# hw_interface_board.net
KiCad netlist of a schematic drawn in EAGLE
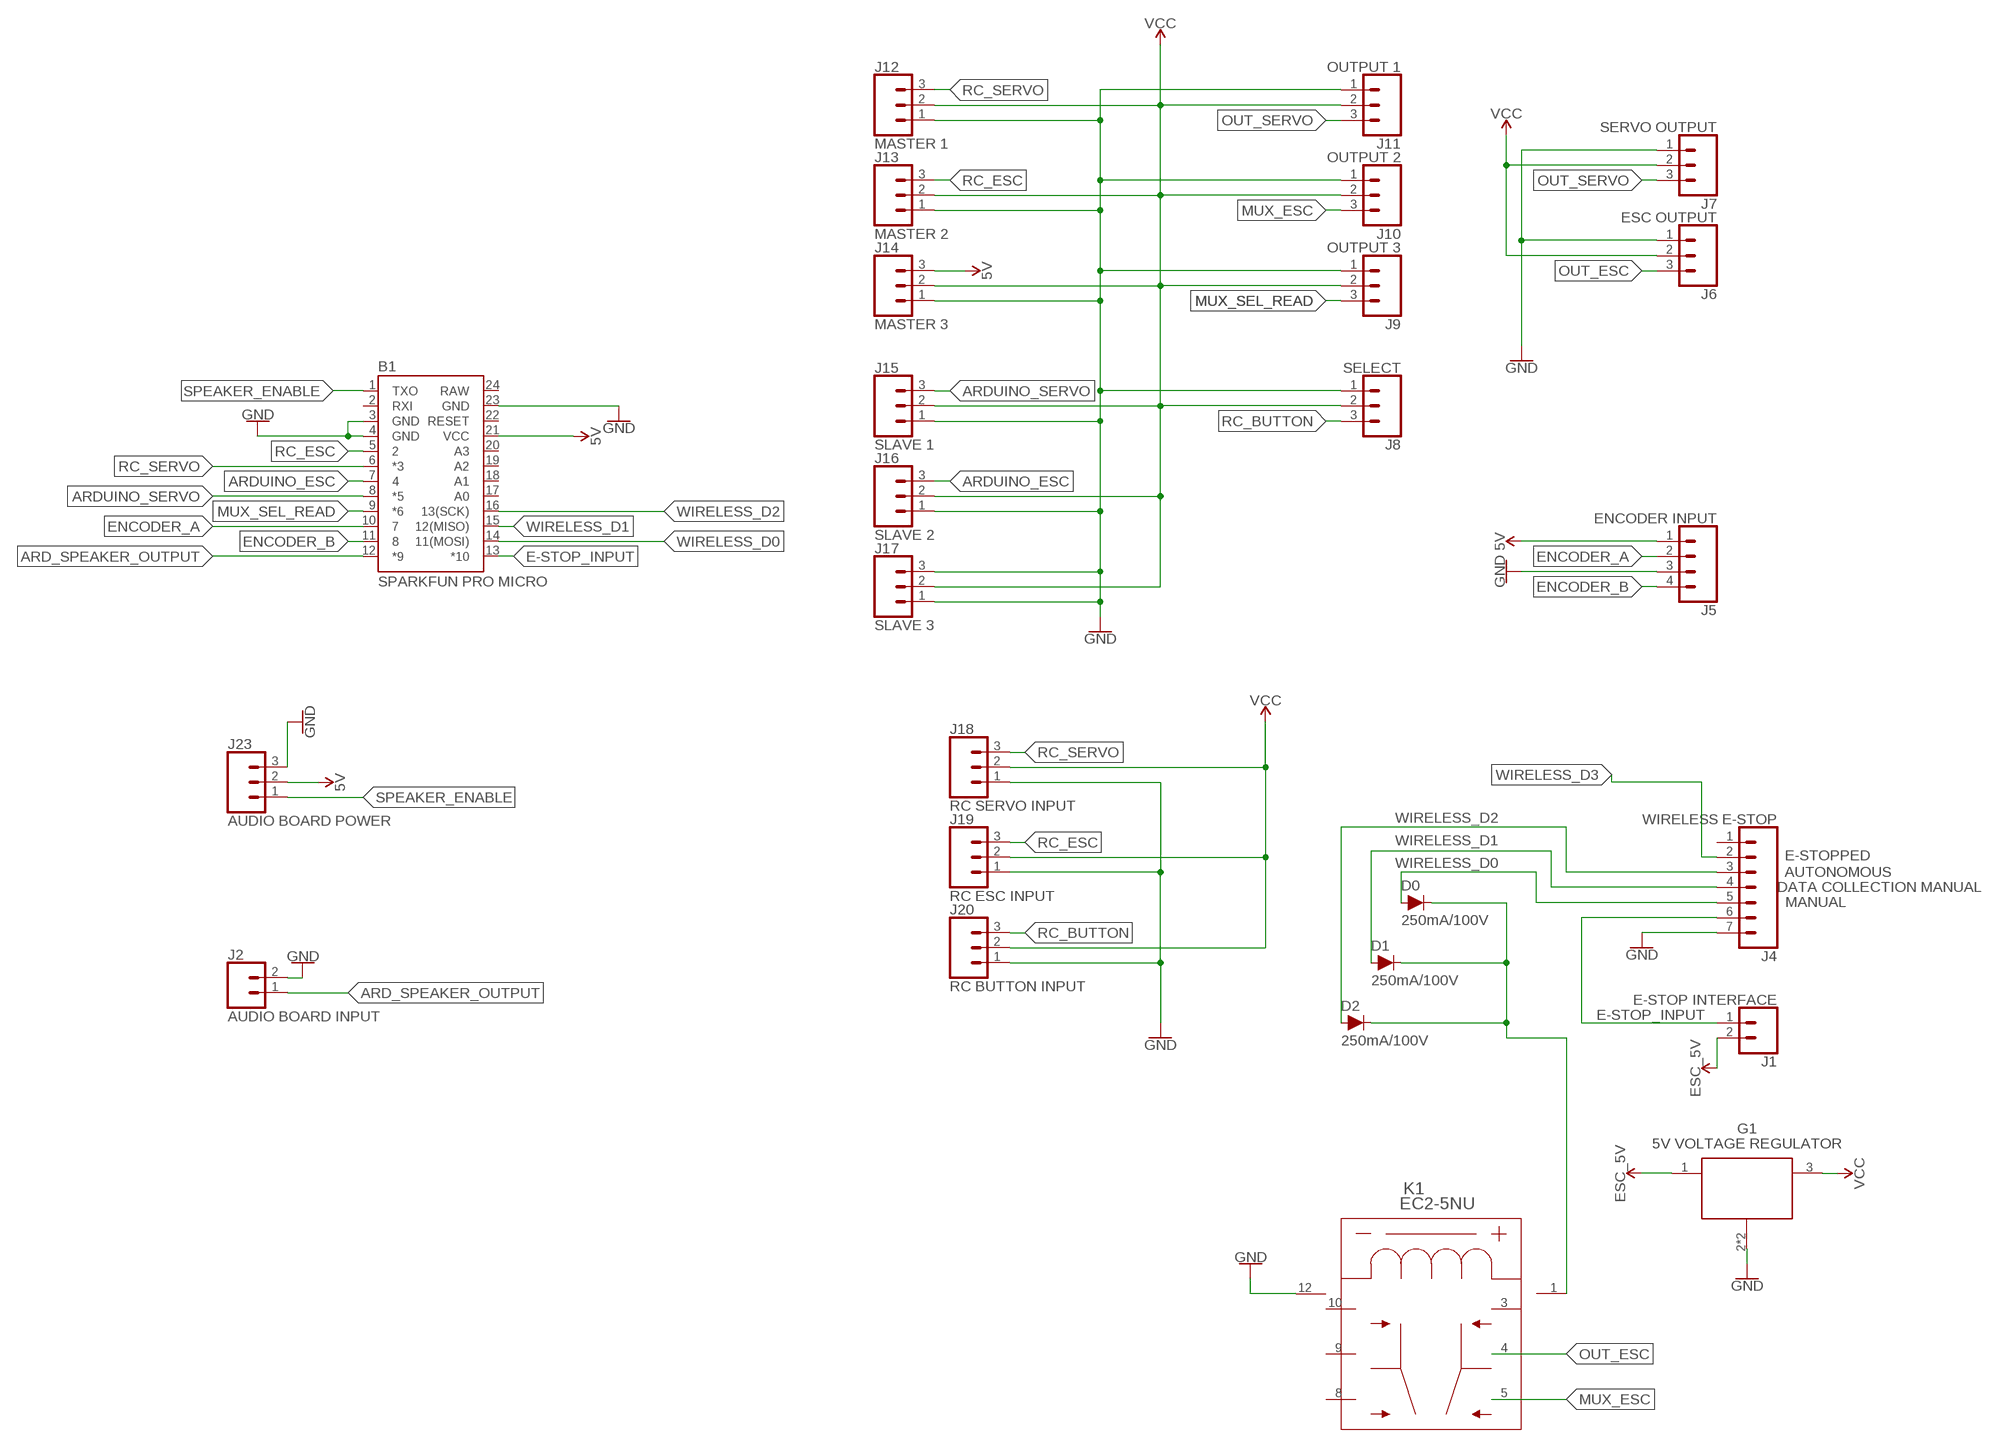
[diagram p0: schematic, sheet 1]

(export (version "E")
  (design (tool "Eeschema 10.0.6"))
  (components
    (comp (ref "B1")
      (value "SPARKFUN PRO MICRO")
      (footprint "eagle-import:SPARKFUN_PRO_MICRO")
      (libsource (lib "eagle-import") (part "SPARKFUN_PRO_MICRO"))
    )
    (comp (ref "D0")
      (value "250mA/100V")
      (footprint "eagle-import:SOD-323")
      (libsource (lib "eagle-import") (part "DIODE-BAS16J"))
    )
    (comp (ref "D1")
      (value "250mA/100V")
      (footprint "eagle-import:SOD-323")
      (libsource (lib "eagle-import") (part "DIODE-BAS16J"))
    )
    (comp (ref "D2")
      (value "250mA/100V")
      (footprint "eagle-import:SOD-323")
      (libsource (lib "eagle-import") (part "DIODE-BAS16J"))
    )
    (comp (ref "G1")
      (value "5V VOLTAGE REGULATOR")
      (footprint "eagle-import:SOT89")
      (libsource (lib "eagle-import") (part "VOLTAGE_REG"))
    )
    (comp (ref "J1")
      (value "E-STOP INTERFACE")
      (footprint "eagle-import:1X02")
      (libsource (lib "eagle-import") (part "CONN_02"))
    )
    (comp (ref "J2")
      (value "AUDIO BOARD INPUT")
      (footprint "eagle-import:1X02")
      (libsource (lib "eagle-import") (part "CONN_02"))
    )
    (comp (ref "J4")
      (value "WIRELESS E-STOP")
      (footprint "eagle-import:1X07")
      (libsource (lib "eagle-import") (part "CONN_07"))
    )
    (comp (ref "J5")
      (value "ENCODER INPUT")
      (footprint "eagle-import:1X04")
      (libsource (lib "eagle-import") (part "CONN_04"))
    )
    (comp (ref "J6")
      (value "ESC OUTPUT")
      (footprint "eagle-import:1X03")
      (libsource (lib "eagle-import") (part "CONN_03"))
    )
    (comp (ref "J7")
      (value "SERVO OUTPUT")
      (footprint "eagle-import:1X03")
      (libsource (lib "eagle-import") (part "CONN_03"))
    )
    (comp (ref "J8")
      (value "SELECT")
      (footprint "eagle-import:1X03")
      (libsource (lib "eagle-import") (part "CONN_03"))
    )
    (comp (ref "J9")
      (value "OUTPUT 3")
      (footprint "eagle-import:1X03")
      (libsource (lib "eagle-import") (part "CONN_03"))
    )
    (comp (ref "J10")
      (value "OUTPUT 2")
      (footprint "eagle-import:1X03")
      (libsource (lib "eagle-import") (part "CONN_03"))
    )
    (comp (ref "J11")
      (value "OUTPUT 1")
      (footprint "eagle-import:1X03")
      (libsource (lib "eagle-import") (part "CONN_03"))
    )
    (comp (ref "J12")
      (value "MASTER 1")
      (footprint "eagle-import:1X03")
      (libsource (lib "eagle-import") (part "CONN_03"))
    )
    (comp (ref "J13")
      (value "MASTER 2")
      (footprint "eagle-import:1X03")
      (libsource (lib "eagle-import") (part "CONN_03"))
    )
    (comp (ref "J14")
      (value "MASTER 3")
      (footprint "eagle-import:1X03")
      (libsource (lib "eagle-import") (part "CONN_03"))
    )
    (comp (ref "J15")
      (value "SLAVE 1")
      (footprint "eagle-import:1X03")
      (libsource (lib "eagle-import") (part "CONN_03"))
    )
    (comp (ref "J16")
      (value "SLAVE 2")
      (footprint "eagle-import:1X03")
      (libsource (lib "eagle-import") (part "CONN_03"))
    )
    (comp (ref "J17")
      (value "SLAVE 3")
      (footprint "eagle-import:1X03")
      (libsource (lib "eagle-import") (part "CONN_03"))
    )
    (comp (ref "J18")
      (value "RC SERVO INPUT")
      (footprint "eagle-import:1X03")
      (libsource (lib "eagle-import") (part "CONN_03"))
    )
    (comp (ref "J19")
      (value "RC ESC INPUT")
      (footprint "eagle-import:1X03")
      (libsource (lib "eagle-import") (part "CONN_03"))
    )
    (comp (ref "J20")
      (value "RC BUTTON INPUT")
      (footprint "eagle-import:1X03")
      (libsource (lib "eagle-import") (part "CONN_03"))
    )
    (comp (ref "J23")
      (value "AUDIO BOARD POWER")
      (footprint "eagle-import:1X03")
      (libsource (lib "eagle-import") (part "CONN_03"))
    )
    (comp (ref "K1")
      (value "EC2-5NU")
      (footprint "eagle-import:EC2NU")
      (fields (field (name "MANUFACTURER_PART_NUMBER") "EC25NU"))
      (libsource (lib "eagle-import") (part "EC2-5NU"))
    )
  )
  (nets
    (net (code "1") (name "/RAW") (class "Default")
      (node (ref "B1") (pin "24") (pinfunction "RAW_24") (pintype "power_in"))
    )
    (net (code "2") (name "5V") (class "Default")
      (node (ref "B1") (pin "21") (pinfunction "VCC_21") (pintype "power_in"))
      (node (ref "J14") (pin "3") (pinfunction "3_3") (pintype "passive"))
      (node (ref "J23") (pin "2") (pinfunction "2_2") (pintype "passive"))
      (node (ref "J5") (pin "1") (pinfunction "1_1") (pintype "passive"))
    )
    (net (code "3") (name "ARDUINO_ESC") (class "Default")
      (node (ref "B1") (pin "7") (pinfunction "4_7") (pintype "bidirectional"))
      (node (ref "J16") (pin "3") (pinfunction "3_3") (pintype "passive"))
    )
    (net (code "4") (name "ARDUINO_SERVO") (class "Default")
      (node (ref "B1") (pin "8") (pinfunction "*5_8") (pintype "bidirectional"))
      (node (ref "J15") (pin "3") (pinfunction "3_3") (pintype "passive"))
    )
    (net (code "5") (name "ARD_SPEAKER_OUTPUT") (class "Default")
      (node (ref "B1") (pin "12") (pinfunction "*9_12") (pintype "bidirectional"))
      (node (ref "J2") (pin "1") (pinfunction "1_1") (pintype "passive"))
    )
    (net (code "6") (name "E-STOP_INPUT") (class "Default")
      (node (ref "B1") (pin "13") (pinfunction "*10_13") (pintype "bidirectional"))
      (node (ref "J1") (pin "1") (pinfunction "1_1") (pintype "passive"))
      (node (ref "J4") (pin "6") (pinfunction "6_6") (pintype "passive"))
    )
    (net (code "7") (name "ENCODER_A") (class "Default")
      (node (ref "B1") (pin "10") (pinfunction "7_10") (pintype "bidirectional"))
      (node (ref "J5") (pin "2") (pinfunction "2_2") (pintype "passive"))
    )
    (net (code "8") (name "ENCODER_B") (class "Default")
      (node (ref "B1") (pin "11") (pinfunction "8_11") (pintype "bidirectional"))
      (node (ref "J5") (pin "4") (pinfunction "4_4") (pintype "passive"))
    )
    (net (code "9") (name "ESC_5V") (class "Default")
      (node (ref "D0") (pin "C") (pinfunction "C_C") (pintype "passive"))
      (node (ref "D1") (pin "C") (pinfunction "C_C") (pintype "passive"))
      (node (ref "D2") (pin "C") (pinfunction "C_C") (pintype "passive"))
      (node (ref "G1") (pin "1") (pinfunction "OUTPUT_1") (pintype "passive"))
      (node (ref "J1") (pin "2") (pinfunction "2_2") (pintype "passive"))
      (node (ref "K1") (pin "1") (pinfunction "1_1") (pintype "passive"))
    )
    (net (code "10") (name "GND") (class "Default")
      (node (ref "B1") (pin "23") (pinfunction "GND_23") (pintype "power_in"))
      (node (ref "B1") (pin "3") (pinfunction "GND_3") (pintype "power_in"))
      (node (ref "B1") (pin "4") (pinfunction "GND_4") (pintype "power_in"))
      (node (ref "G1") (pin "2") (pinfunction "GND_2") (pintype "passive"))
      (node (ref "G1") (pin "2@1") (pinfunction "GND_2@1") (pintype "passive"))
      (node (ref "J10") (pin "1") (pinfunction "1_1") (pintype "passive"))
      (node (ref "J11") (pin "1") (pinfunction "1_1") (pintype "passive"))
      (node (ref "J12") (pin "1") (pinfunction "1_1") (pintype "passive"))
      (node (ref "J13") (pin "1") (pinfunction "1_1") (pintype "passive"))
      (node (ref "J14") (pin "1") (pinfunction "1_1") (pintype "passive"))
      (node (ref "J15") (pin "1") (pinfunction "1_1") (pintype "passive"))
      (node (ref "J16") (pin "1") (pinfunction "1_1") (pintype "passive"))
      (node (ref "J17") (pin "1") (pinfunction "1_1") (pintype "passive"))
      (node (ref "J17") (pin "3") (pinfunction "3_3") (pintype "passive"))
      (node (ref "J18") (pin "1") (pinfunction "1_1") (pintype "passive"))
      (node (ref "J19") (pin "1") (pinfunction "1_1") (pintype "passive"))
      (node (ref "J2") (pin "2") (pinfunction "2_2") (pintype "passive"))
      (node (ref "J20") (pin "1") (pinfunction "1_1") (pintype "passive"))
      (node (ref "J23") (pin "3") (pinfunction "3_3") (pintype "passive"))
      (node (ref "J4") (pin "7") (pinfunction "7_7") (pintype "passive"))
      (node (ref "J5") (pin "3") (pinfunction "3_3") (pintype "passive"))
      (node (ref "J6") (pin "1") (pinfunction "1_1") (pintype "passive"))
      (node (ref "J7") (pin "1") (pinfunction "1_1") (pintype "passive"))
      (node (ref "J8") (pin "1") (pinfunction "1_1") (pintype "passive"))
      (node (ref "J9") (pin "1") (pinfunction "1_1") (pintype "passive"))
      (node (ref "K1") (pin "12") (pinfunction "8_12") (pintype "passive"))
    )
    (net (code "11") (name "MUX_ESC") (class "Default")
      (node (ref "J10") (pin "3") (pinfunction "3_3") (pintype "passive"))
      (node (ref "K1") (pin "5") (pinfunction "4_5") (pintype "passive"))
    )
    (net (code "12") (name "MUX_SEL_READ") (class "Default")
      (node (ref "B1") (pin "9") (pinfunction "*6_9") (pintype "bidirectional"))
      (node (ref "J9") (pin "3") (pinfunction "3_3") (pintype "passive"))
    )
    (net (code "13") (name "OUT_ESC") (class "Default")
      (node (ref "J6") (pin "3") (pinfunction "3_3") (pintype "passive"))
      (node (ref "K1") (pin "4") (pinfunction "3_4") (pintype "passive"))
    )
    (net (code "14") (name "OUT_SERVO") (class "Default")
      (node (ref "J11") (pin "3") (pinfunction "3_3") (pintype "passive"))
      (node (ref "J7") (pin "3") (pinfunction "3_3") (pintype "passive"))
    )
    (net (code "15") (name "RC_BUTTON") (class "Default")
      (node (ref "J20") (pin "3") (pinfunction "3_3") (pintype "passive"))
      (node (ref "J8") (pin "3") (pinfunction "3_3") (pintype "passive"))
    )
    (net (code "16") (name "RC_ESC") (class "Default")
      (node (ref "B1") (pin "5") (pinfunction "2_5") (pintype "bidirectional"))
      (node (ref "J13") (pin "3") (pinfunction "3_3") (pintype "passive"))
      (node (ref "J19") (pin "3") (pinfunction "3_3") (pintype "passive"))
    )
    (net (code "17") (name "RC_SERVO") (class "Default")
      (node (ref "B1") (pin "6") (pinfunction "*3_6") (pintype "bidirectional"))
      (node (ref "J12") (pin "3") (pinfunction "3_3") (pintype "passive"))
      (node (ref "J18") (pin "3") (pinfunction "3_3") (pintype "passive"))
    )
    (net (code "18") (name "SPEAKER_ENABLE") (class "Default")
      (node (ref "B1") (pin "1") (pinfunction "TXO_1") (pintype "bidirectional"))
      (node (ref "J23") (pin "1") (pinfunction "1_1") (pintype "passive"))
    )
    (net (code "19") (name "VCC") (class "Default")
      (node (ref "G1") (pin "3") (pinfunction "INPUT_3") (pintype "passive"))
      (node (ref "J10") (pin "2") (pinfunction "2_2") (pintype "passive"))
      (node (ref "J11") (pin "2") (pinfunction "2_2") (pintype "passive"))
      (node (ref "J12") (pin "2") (pinfunction "2_2") (pintype "passive"))
      (node (ref "J13") (pin "2") (pinfunction "2_2") (pintype "passive"))
      (node (ref "J14") (pin "2") (pinfunction "2_2") (pintype "passive"))
      (node (ref "J15") (pin "2") (pinfunction "2_2") (pintype "passive"))
      (node (ref "J16") (pin "2") (pinfunction "2_2") (pintype "passive"))
      (node (ref "J17") (pin "2") (pinfunction "2_2") (pintype "passive"))
      (node (ref "J18") (pin "2") (pinfunction "2_2") (pintype "passive"))
      (node (ref "J19") (pin "2") (pinfunction "2_2") (pintype "passive"))
      (node (ref "J20") (pin "2") (pinfunction "2_2") (pintype "passive"))
      (node (ref "J6") (pin "2") (pinfunction "2_2") (pintype "passive"))
      (node (ref "J7") (pin "2") (pinfunction "2_2") (pintype "passive"))
      (node (ref "J8") (pin "2") (pinfunction "2_2") (pintype "passive"))
      (node (ref "J9") (pin "2") (pinfunction "2_2") (pintype "passive"))
    )
    (net (code "20") (name "WIRELESS_D0") (class "Default")
      (node (ref "B1") (pin "14") (pinfunction "11(MOSI)_14") (pintype "bidirectional"))
      (node (ref "D0") (pin "A") (pinfunction "A_A") (pintype "passive"))
      (node (ref "J4") (pin "5") (pinfunction "5_5") (pintype "passive"))
    )
    (net (code "21") (name "WIRELESS_D1") (class "Default")
      (node (ref "B1") (pin "15") (pinfunction "12(MISO)_15") (pintype "bidirectional"))
      (node (ref "D1") (pin "A") (pinfunction "A_A") (pintype "passive"))
      (node (ref "J4") (pin "4") (pinfunction "4_4") (pintype "passive"))
    )
    (net (code "22") (name "WIRELESS_D2") (class "Default")
      (node (ref "B1") (pin "16") (pinfunction "13(SCK)_16") (pintype "bidirectional"))
      (node (ref "D2") (pin "A") (pinfunction "A_A") (pintype "passive"))
      (node (ref "J4") (pin "3") (pinfunction "3_3") (pintype "passive"))
    )
    (net (code "23") (name "WIRELESS_D3") (class "Default")
      (node (ref "J4") (pin "2") (pinfunction "2_2") (pintype "passive"))
    )
    (net (code "24") (name "unconnected-(B1-A0-Pad17)") (class "Default")
      (node (ref "B1") (pin "17") (pinfunction "A0_17") (pintype "bidirectional"))
    )
    (net (code "25") (name "unconnected-(B1-A1-Pad18)") (class "Default")
      (node (ref "B1") (pin "18") (pinfunction "A1_18") (pintype "bidirectional"))
    )
    (net (code "26") (name "unconnected-(B1-A2-Pad19)") (class "Default")
      (node (ref "B1") (pin "19") (pinfunction "A2_19") (pintype "bidirectional"))
    )
    (net (code "27") (name "unconnected-(B1-A3-Pad20)") (class "Default")
      (node (ref "B1") (pin "20") (pinfunction "A3_20") (pintype "bidirectional"))
    )
    (net (code "28") (name "unconnected-(B1-RESET-Pad22)") (class "Default")
      (node (ref "B1") (pin "22") (pinfunction "RESET_22") (pintype "bidirectional"))
    )
    (net (code "29") (name "unconnected-(B1-RXI-Pad2)") (class "Default")
      (node (ref "B1") (pin "2") (pinfunction "RXI_2") (pintype "bidirectional"))
    )
    (net (code "30") (name "unconnected-(J4-Pad1)") (class "Default")
      (node (ref "J4") (pin "1") (pinfunction "1_1") (pintype "passive"))
    )
    (net (code "31") (name "unconnected-(K1-2-Pad3)") (class "Default")
      (node (ref "K1") (pin "3") (pinfunction "2_3") (pintype "passive"))
    )
    (net (code "32") (name "unconnected-(K1-5-Pad8)") (class "Default")
      (node (ref "K1") (pin "8") (pinfunction "5_8") (pintype "passive"))
    )
    (net (code "33") (name "unconnected-(K1-6-Pad9)") (class "Default")
      (node (ref "K1") (pin "9") (pinfunction "6_9") (pintype "passive"))
    )
    (net (code "34") (name "unconnected-(K1-7-Pad10)") (class "Default")
      (node (ref "K1") (pin "10") (pinfunction "7_10") (pintype "passive"))
    )
  )
)
